# 03_-_BLOCK_DIAGRAM.net
KiCad netlist of a schematic drawn in Altium Designer
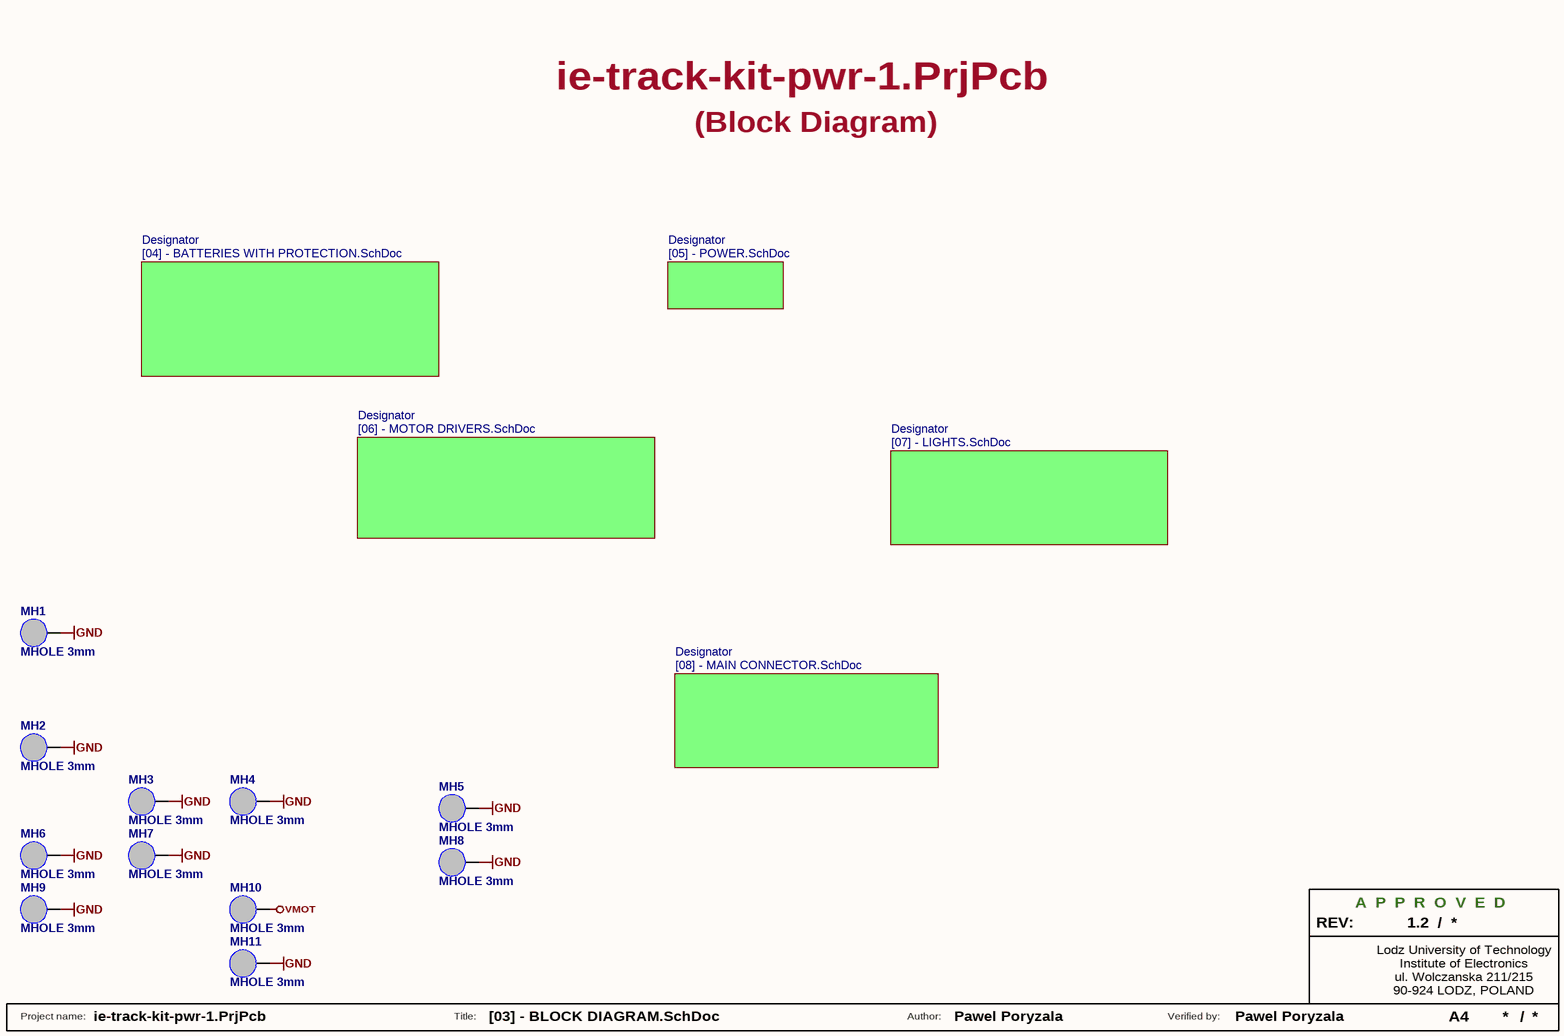
[diagram p0: [03] - BLOCK DIAGRAM.SchDoc]

(export (version "E")
  (design (tool "Eeschema 10.0.6"))
  (components
    (comp (ref "MH1")
      (value "MHOLE 3mm")
      (footprint "3mm screw drill I")
      (description "3mm Mounting Hole")
      (libsource (lib "mechanical_other") (part "MHOLE_3MM"))
    )
    (comp (ref "MH2")
      (value "MHOLE 3mm")
      (footprint "3mm screw drill I")
      (description "3mm Mounting Hole")
      (libsource (lib "mechanical_other") (part "MHOLE_3MM"))
    )
    (comp (ref "MH3")
      (value "MHOLE 3mm")
      (footprint "3mm screw drill I")
      (description "3mm Mounting Hole")
      (libsource (lib "mechanical_other") (part "MHOLE_3MM"))
    )
    (comp (ref "MH4")
      (value "MHOLE 3mm")
      (footprint "3mm screw drill I")
      (description "3mm Mounting Hole")
      (libsource (lib "mechanical_other") (part "MHOLE_3MM"))
    )
    (comp (ref "MH5")
      (value "MHOLE 3mm")
      (footprint "3mm screw drill I")
      (description "3mm Mounting Hole")
      (libsource (lib "mechanical_other") (part "MHOLE_3MM"))
    )
    (comp (ref "MH6")
      (value "MHOLE 3mm")
      (footprint "3mm screw drill I")
      (description "3mm Mounting Hole")
      (libsource (lib "mechanical_other") (part "MHOLE_3MM"))
    )
    (comp (ref "MH7")
      (value "MHOLE 3mm")
      (footprint "3mm screw drill I")
      (description "3mm Mounting Hole")
      (libsource (lib "mechanical_other") (part "MHOLE_3MM"))
    )
    (comp (ref "MH8")
      (value "MHOLE 3mm")
      (footprint "3mm screw drill I")
      (description "3mm Mounting Hole")
      (libsource (lib "mechanical_other") (part "MHOLE_3MM"))
    )
    (comp (ref "MH9")
      (value "MHOLE 3mm")
      (footprint "3mm screw drill I")
      (description "3mm Mounting Hole")
      (libsource (lib "mechanical_other") (part "MHOLE_3MM"))
    )
    (comp (ref "MH10")
      (value "MHOLE 3mm")
      (footprint "3mm screw drill I")
      (description "3mm Mounting Hole")
      (libsource (lib "mechanical_other") (part "MHOLE_3MM"))
    )
    (comp (ref "MH11")
      (value "MHOLE 3mm")
      (footprint "3mm screw drill I")
      (description "3mm Mounting Hole")
      (libsource (lib "mechanical_other") (part "MHOLE_3MM"))
    )
  )
  (nets
    (net (code "1") (name "GND") (class "Default")
      (node (ref "MH1") (pin "1") (pinfunction "GND_1") (pintype "passive"))
      (node (ref "MH11") (pin "1") (pinfunction "GND_1") (pintype "passive"))
      (node (ref "MH2") (pin "1") (pinfunction "GND_1") (pintype "passive"))
      (node (ref "MH3") (pin "1") (pinfunction "GND_1") (pintype "passive"))
      (node (ref "MH4") (pin "1") (pinfunction "GND_1") (pintype "passive"))
      (node (ref "MH5") (pin "1") (pinfunction "GND_1") (pintype "passive"))
      (node (ref "MH6") (pin "1") (pinfunction "GND_1") (pintype "passive"))
      (node (ref "MH7") (pin "1") (pinfunction "GND_1") (pintype "passive"))
      (node (ref "MH8") (pin "1") (pinfunction "GND_1") (pintype "passive"))
      (node (ref "MH9") (pin "1") (pinfunction "GND_1") (pintype "passive"))
    )
    (net (code "2") (name "VMOT") (class "Default")
      (node (ref "MH10") (pin "1") (pinfunction "GND_1") (pintype "passive"))
    )
  )
)
